# SiC462_12V_6A.net
KiCad netlist of a schematic drawn in Altium Designer
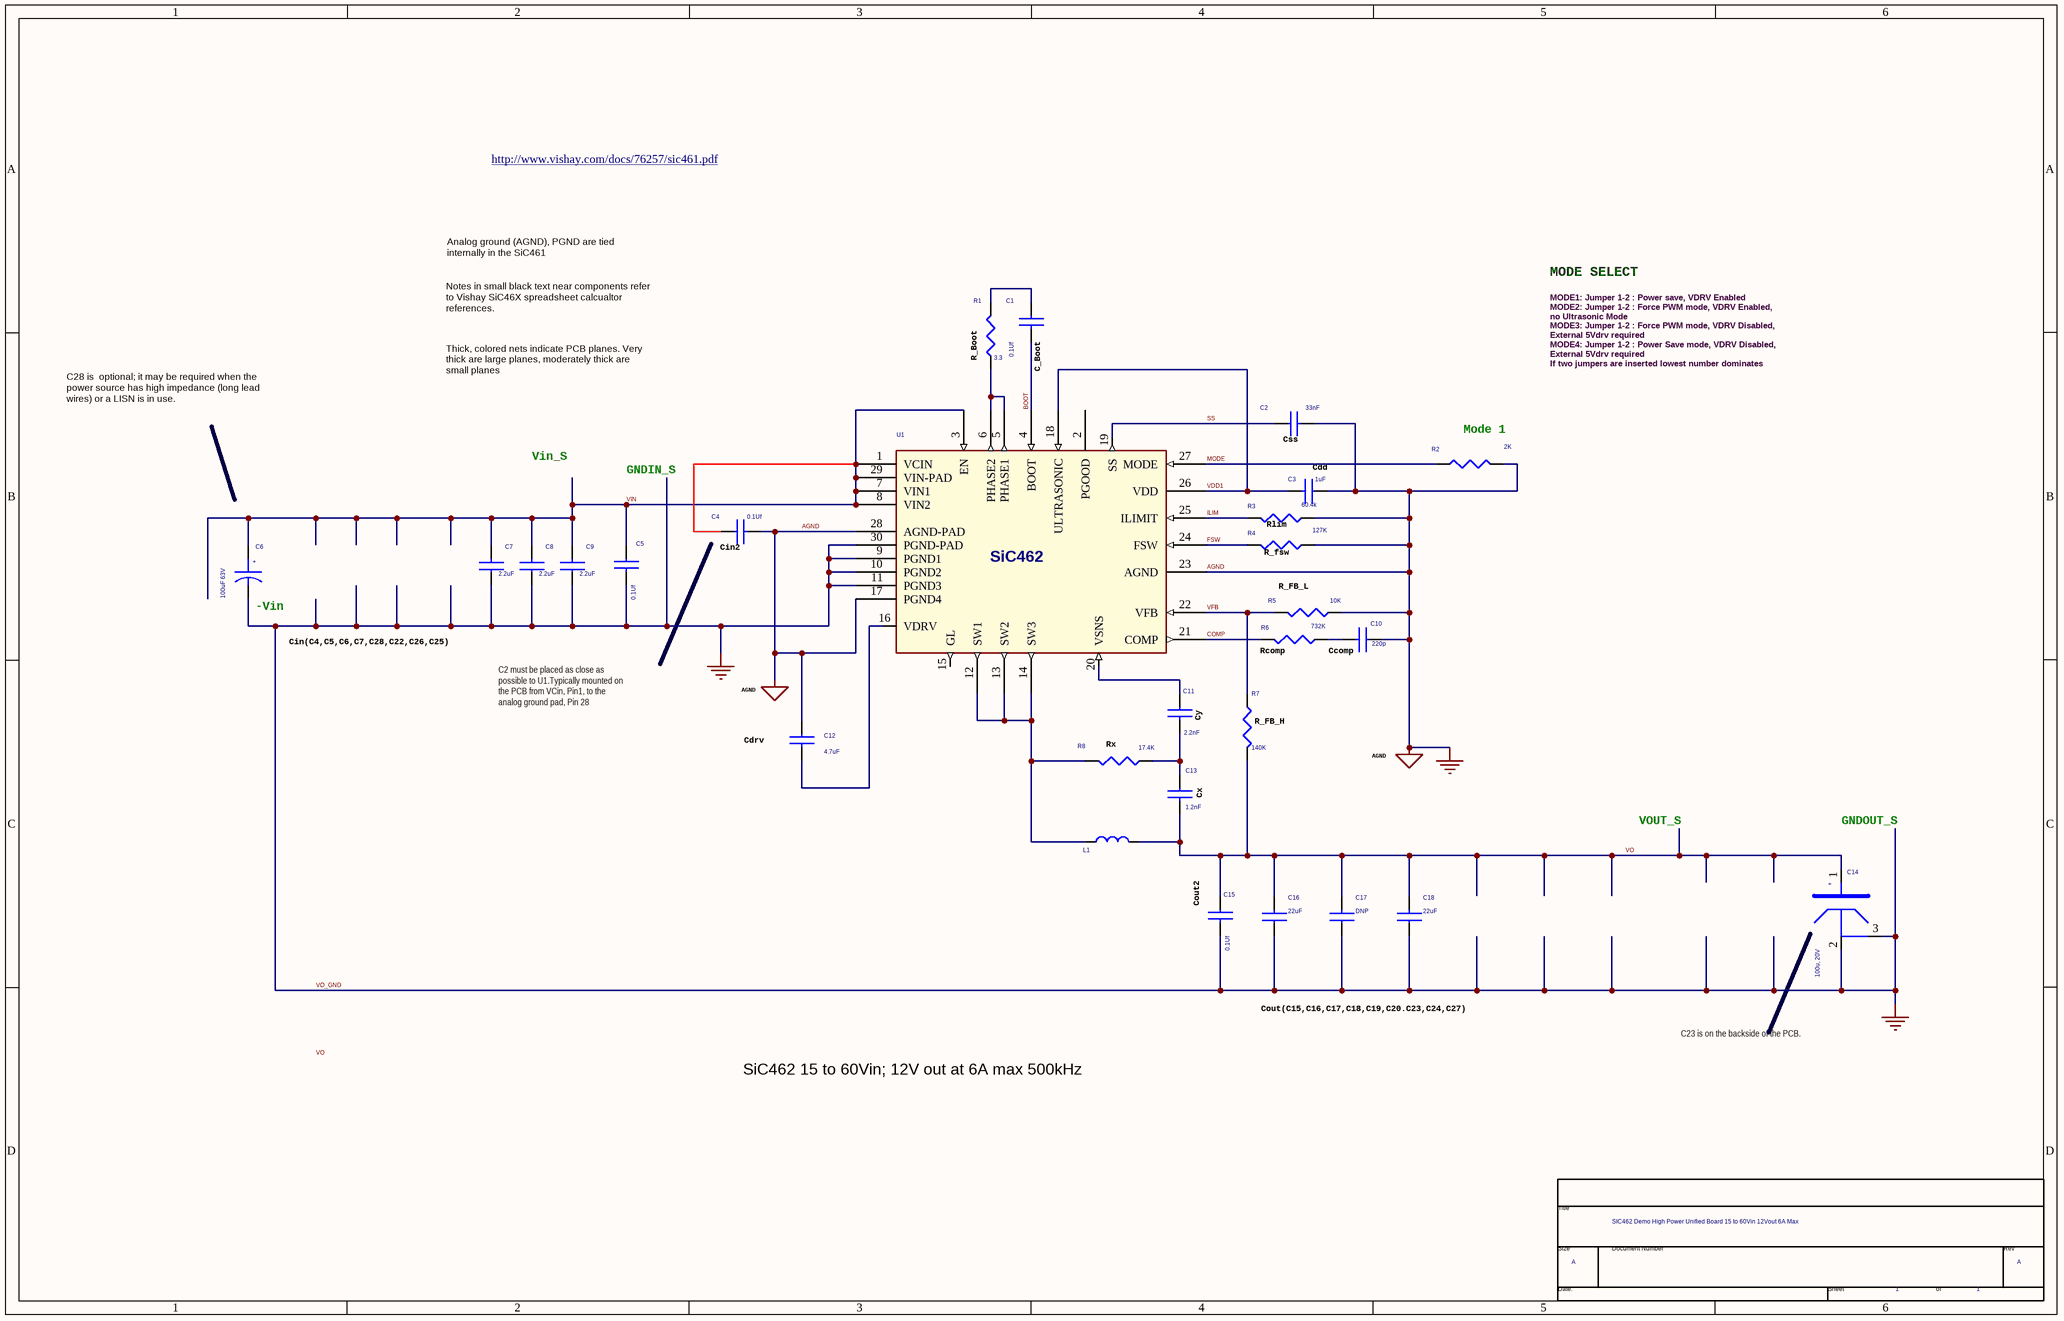
[diagram p0: SiC462 12V 6A.SchDoc]

(export (version "E")
  (design (tool "Eeschema 10.0.6"))
  (components
    (comp (ref "*")
      (value "TitleBlock0")
      (fields
        (field (name "REVCODE") "A")
        (field (name "TITLE") "SIC462 Demo High Power Unified Board 15 to 60Vin 12Vout 6A Max")
        (field (name "PAGE SIZE") "A")
        (field (name "PAGE NUMBER") "1")
        (field (name "PAGE COUNT") "1")
      )
      (libsource (lib "*") (part "TitleBlock0"))
    )
    (comp (ref "C1")
      (value "0.1Uf")
      (footprint "RR_0603")
      (description "Ceramic Cap, 0.1uF,100volts, X7S, 10%, 0603")
      (fields (field (name "TOLERANCE") "10%") (field (name "MFR") "Murata Electronics"))
      (libsource (lib "*") (part "CAP NP"))
    )
    (comp (ref "C2")
      (value "33nF")
      (footprint "RR_0603")
      (description "Ceramic Cap, 0.033uF,50V,X7R,0603,10%")
      (fields (field (name "MFR PART NUMBER") "VJ0603Y333KXACW1BC") (field (name "VOLTAGE") "50V"))
      (libsource (lib "*") (part "CAP NP"))
    )
    (comp (ref "C3")
      (value "1uF")
      (footprint "RR_0603")
      (description "Ceramic Cap, 1uF,50V, X7R,0603,10%")
      (fields
        (field (name "MANUFACTURER") "Taiyo Yuden")
        (field (name "MANUFACTURER PART") "UMK107AB7105KA-T")
      )
      (libsource (lib "*") (part "CAP NP"))
    )
    (comp (ref "C4")
      (value "0.1Uf")
      (footprint "RR_0603")
      (description "Ceramic Cap, 0.1uF,100volts, X7S, 10%, 0603")
      (fields (field (name "TOLERANCE") "10%") (field (name "MFR") "Murata Electronics"))
      (libsource (lib "*") (part "CAP NP"))
    )
    (comp (ref "C5")
      (value "0.1Uf")
      (footprint "RR_0603")
      (description "Ceramic Cap, 0.1uF,100volts, X7S, 10%, 0603")
      (fields
        (field (name "MFR PART NUMBER") "C1608X7S2A104K080AB")
        (field (name "MFR") "Murata Electronics")
      )
      (libsource (lib "*") (part "CAP NP"))
    )
    (comp (ref "C6")
      (value "100uF 63V")
      (footprint "RR_CAP-RAD-D10x9")
      (description "CAP, alum, 100uF, 63volt, 105C, 10x12, 4khr")
      (fields (field (name "MFR PART NUMBER") "MAL215058101E3") (field (name "MFR") "Vishay"))
      (libsource (lib "*") (part "CAP POL"))
    )
    (comp (ref "C7")
      (value "2.2uF")
      (footprint "RR_1210")
      (description "Ceramic Cap, 2.2uF,100volts, X7R, 10%, 1210")
      (fields (field (name "MFR PART NUMBER") "GRM32ER72A225KA35K") (field (name "MFR") "Murata Electronics"))
      (libsource (lib "*") (part "CAP NP"))
    )
    (comp (ref "C8")
      (value "2.2uF")
      (footprint "RR_1210")
      (description "Ceramic Cap, 2.2uF,100volts, X7R, 10%, 1210")
      (fields (field (name "MFR") "Murata Electronics") (field (name "MFR PART NUMBER") "GRM32ER72A225KA35K"))
      (libsource (lib "*") (part "CAP NP"))
    )
    (comp (ref "C9")
      (value "2.2uF")
      (footprint "RR_1210")
      (description "Ceramic Cap, 2.2uF,100volts, X7R, 10%, 1210")
      (fields (field (name "MFR PART NUMBER") "GRM32ER72A225KA35K") (field (name "MFR") "Murata Electronics"))
      (libsource (lib "*") (part "CAP NP"))
    )
    (comp (ref "C10")
      (value "220p")
      (footprint "RR_0603")
      (description "Ceramic Cap, 220p,100V,COG,0603, 5%")
      (fields (field (name "MANUFACTURER") "Vishay") (field (name "MANUFACTURER PART") "VJ0603A221JXBPW1BC"))
      (libsource (lib "*") (part "CAP NP"))
    )
    (comp (ref "C11")
      (value "2.2nF")
      (footprint "RR_0603")
      (description "Ceramic Cap, 2200pF,100V,X7R,0603, 5%")
      (fields (field (name "MFR") "Vishay") (field (name "TOLERANCE") "5%"))
      (libsource (lib "*") (part "CAP NP"))
    )
    (comp (ref "C12")
      (value "4.7uF")
      (footprint "RR_1206")
      (description "Ceramic Cap, 4.7uF,25V,X6S,10%,0603")
      (fields (field (name "MFR") "Murata") (field (name "TOLERANCE") "10%"))
      (libsource (lib "*") (part "CAP NP"))
    )
    (comp (ref "C13")
      (value "1.2nF")
      (footprint "RR_0603")
      (description "Ceramic Cap, 1.2nF,100V,X7R,0805, 10%")
      (fields (field (name "MANUFACTURER") "Vishay") (field (name "MANUFACTURER PART") "VJ0805Y122KXBPW1BC"))
      (libsource (lib "*") (part "CAP NP"))
    )
    (comp (ref "C14")
      (value "100u, 20V")
      (footprint "RR_CAP-RAD-D10x9")
      (description "Polymer SMD 20volts 100uF ESR 55mohm 7343")
      (fields (field (name "MFR PART NUMBER") "20TQC100MYF") (field (name "MFR") "Panasonic"))
      (libsource (lib "*") (part "CAP, TA-P,V,470u, 2V_0"))
    )
    (comp (ref "C15")
      (value "0.1Uf")
      (footprint "RR_0805")
      (description "Ceramic Cap, 0.1uF,100volts, X7S, 10%, 0603")
      (fields
        (field (name "MFR PART NUMBER") "C1608X7S2A104K080AB")
        (field (name "MFR") "Murata Electronics")
      )
      (libsource (lib "*") (part "CAP NP"))
    )
    (comp (ref "C16")
      (value "22uF")
      (footprint "RR_1206")
      (description "Ceramic Cap, 22uF,25volts,X7R,10%,1206")
      (fields (field (name "MFR") "AVX Corporation") (field (name "TOLERANCE") "10%"))
      (libsource (lib "*") (part "CAP NP"))
    )
    (comp (ref "C17")
      (value "DNP")
      (footprint "RR_1206")
      (description "Ceramic Cap, 22uF,25volts,X7R,10%,1206")
      (fields (field (name "MFR PART NUMBER") "12061C225KAT2A") (field (name "VOLTAGE") "100V"))
      (libsource (lib "*") (part "CAP NP"))
    )
    (comp (ref "C18")
      (value "22uF")
      (footprint "RR_1206")
      (description "Ceramic Cap, 22uF,25volts,X7R,10%,1206")
      (fields (field (name "MFR") "AVX Corporation") (field (name "TOLERANCE") "10%"))
      (libsource (lib "*") (part "CAP NP"))
    )
    (comp (ref "L1")
      (value "~")
      (footprint "RR_IND_CMD_12x12")
      (description "INDUCTOR, 3.3uH,20%,14m DCR,18.6A Saturation")
      (fields (field (name "MFR PART NUMBER") "IHLP4040DZER100M01") (field (name "MANUFACTURER") "Vishay"))
      (libsource (lib "*") (part "IND"))
    )
    (comp (ref "R1")
      (value "3.3")
      (footprint "RR_0603")
      (description "SMD,3.3Ohm, 1% 0603")
      (fields
        (field (name "MAN PART NUMBER") "CRCW06033R30FKEA")
        (field (name "MANUFACTURER PART") "CRCW06030000ZSTA")
      )
      (libsource (lib "*") (part "RESISTOR"))
    )
    (comp (ref "R2")
      (value "2K")
      (footprint "RR_0603")
      (description "SMD,2K,1%,0603")
      (fields (field (name "MANUFACTURER") "Vishay") (field (name "MANUFACTURER PART") "CRCW06032K00FKEB"))
      (libsource (lib "*") (part "RESISTOR"))
    )
    (comp (ref "R3")
      (value "60.4k")
      (footprint "RR_0603")
      (description "SMD,60.4K,1%,0603")
      (fields (field (name "MANUFACTURER") "Vishay") (field (name "MANUFACTURER PART") "CRCW060360K4FKEA"))
      (libsource (lib "*") (part "RESISTOR"))
    )
    (comp (ref "R4")
      (value "127K")
      (footprint "RR_0603")
      (description "SMD,127K,1%,0603 100PPM")
      (fields (field (name "MANUFACTURER") "Vishay") (field (name "MANUFACTURER PART") "CRCW0603127KFKEA"))
      (libsource (lib "*") (part "RESISTOR"))
    )
    (comp (ref "R5")
      (value "10K")
      (footprint "RR_0603")
      (description "SMD,10K,1%,0603")
      (fields (field (name "MANUFACTURER") "Vishay") (field (name "MANUFACTURER PART") "CRCW060310K0FKTA"))
      (libsource (lib "*") (part "RESISTOR"))
    )
    (comp (ref "R6")
      (value "732K")
      (footprint "RR_0603")
      (description "SMD 1/10watt 732 kOhms 1%,0603")
      (fields (field (name "MFR") "Vishay Dale") (field (name "TOLERANCE") "1%"))
      (libsource (lib "*") (part "RESISTOR"))
    )
    (comp (ref "R7")
      (value "140K")
      (footprint "RR_0603")
      (description "SMD 1,10W 140K Ohms 1% 0603")
      (fields (field (name "MANUFACTURER") "Vishay") (field (name "MANUFACTURER PART") "CRCW0603140KFKEA"))
      (libsource (lib "*") (part "RESISTOR"))
    )
    (comp (ref "R8")
      (value "17.4K")
      (footprint "RR_0603")
      (description "Resistors - SMD 1/8watt 17.4Kohms 1% 0805")
      (fields (field (name "MFR") "Vishay Dale") (field (name "TOLERANCE") "1%"))
      (libsource (lib "*") (part "RESISTOR"))
    )
    (comp (ref "U1")
      (value "SiC462")
      (footprint "SIC462")
      (description "4.5~60V,6A, High Voltage microBuck")
      (fields (field (name "MFR") "Vishay") (field (name "MAN PART NUMBER") "SiC462ED-T1-GE3"))
      (libsource (lib "*") (part "SiC462CD-T1-GE3_27"))
    )
  )
  (nets
    (net (code "1") (name "/BOOT") (class "Default")
      (node (ref "C1") (pin "2") (pinfunction "2_2") (pintype "passive"))
      (node (ref "U1") (pin "4") (pinfunction "BOOT_4") (pintype "input"))
    )
    (net (code "2") (name "/COMP") (class "Default")
      (node (ref "R6") (pin "2") (pinfunction "2_2") (pintype "passive"))
      (node (ref "U1") (pin "21") (pinfunction "COMP_21") (pintype "output"))
    )
    (net (code "3") (name "/FSW") (class "Default")
      (node (ref "R4") (pin "2") (pinfunction "2_2") (pintype "passive"))
      (node (ref "U1") (pin "24") (pinfunction "FSW_24") (pintype "input"))
    )
    (net (code "4") (name "/ILIM") (class "Default")
      (node (ref "R3") (pin "2") (pinfunction "2_2") (pintype "passive"))
      (node (ref "U1") (pin "25") (pinfunction "ILIMIT_25") (pintype "input"))
    )
    (net (code "5") (name "/MODE") (class "Default")
      (node (ref "R2") (pin "1") (pinfunction "1_1") (pintype "passive"))
      (node (ref "U1") (pin "27") (pinfunction "MODE_27") (pintype "input"))
    )
    (net (code "6") (name "/SS") (class "Default")
      (node (ref "C2") (pin "1") (pinfunction "1_1") (pintype "passive"))
      (node (ref "U1") (pin "19") (pinfunction "SS_19") (pintype "output"))
    )
    (net (code "7") (name "/VDD1") (class "Default")
      (node (ref "C3") (pin "2") (pinfunction "2_2") (pintype "passive"))
      (node (ref "U1") (pin "18") (pinfunction "ULTRASONIC_18") (pintype "input"))
      (node (ref "U1") (pin "26") (pinfunction "VDD_26") (pintype "power_in"))
    )
    (net (code "8") (name "/VFB") (class "Default")
      (node (ref "R5") (pin "2") (pinfunction "2_2") (pintype "passive"))
      (node (ref "R7") (pin "1") (pinfunction "1_1") (pintype "passive"))
      (node (ref "U1") (pin "22") (pinfunction "VFB_22") (pintype "input"))
    )
    (net (code "9") (name "/VIN") (class "Default")
      (node (ref "C4") (pin "1") (pinfunction "1_1") (pintype "passive"))
      (node (ref "C5") (pin "1") (pinfunction "1_1") (pintype "passive"))
      (node (ref "C6") (pin "1") (pinfunction "1_1") (pintype "passive"))
      (node (ref "C7") (pin "2") (pinfunction "2_2") (pintype "passive"))
      (node (ref "C8") (pin "2") (pinfunction "2_2") (pintype "passive"))
      (node (ref "C9") (pin "2") (pinfunction "2_2") (pintype "passive"))
      (node (ref "U1") (pin "1") (pinfunction "VCIN_1") (pintype "power_in"))
      (node (ref "U1") (pin "29") (pinfunction "VIN-PAD_29") (pintype "power_in"))
      (node (ref "U1") (pin "3") (pinfunction "EN_3") (pintype "input"))
      (node (ref "U1") (pin "7") (pinfunction "VIN1_7") (pintype "power_in"))
      (node (ref "U1") (pin "8") (pinfunction "VIN2_8") (pintype "power_in"))
    )
    (net (code "10") (name "/VO") (class "Default")
      (node (ref "C13") (pin "2") (pinfunction "2_2") (pintype "passive"))
      (node (ref "C14") (pin "1") (pinfunction "1_1") (pintype "passive"))
      (node (ref "C15") (pin "1") (pinfunction "1_1") (pintype "passive"))
      (node (ref "C16") (pin "2") (pinfunction "2_2") (pintype "passive"))
      (node (ref "C17") (pin "2") (pinfunction "2_2") (pintype "passive"))
      (node (ref "C18") (pin "2") (pinfunction "2_2") (pintype "passive"))
      (node (ref "L1") (pin "1") (pinfunction "A_1") (pintype "passive"))
      (node (ref "R7") (pin "2") (pinfunction "2_2") (pintype "passive"))
    )
    (net (code "11") (name "GND") (class "Default")
      (node (ref "C10") (pin "1") (pinfunction "1_1") (pintype "passive"))
      (node (ref "C12") (pin "1") (pinfunction "1_1") (pintype "passive"))
      (node (ref "C14") (pin "2") (pinfunction "2_2") (pintype "passive"))
      (node (ref "C14") (pin "3") (pinfunction "3_3") (pintype "passive"))
      (node (ref "C15") (pin "2") (pinfunction "2_2") (pintype "passive"))
      (node (ref "C16") (pin "1") (pinfunction "1_1") (pintype "passive"))
      (node (ref "C17") (pin "1") (pinfunction "1_1") (pintype "passive"))
      (node (ref "C18") (pin "1") (pinfunction "1_1") (pintype "passive"))
      (node (ref "C2") (pin "2") (pinfunction "2_2") (pintype "passive"))
      (node (ref "C3") (pin "1") (pinfunction "1_1") (pintype "passive"))
      (node (ref "C4") (pin "2") (pinfunction "2_2") (pintype "passive"))
      (node (ref "C5") (pin "2") (pinfunction "2_2") (pintype "passive"))
      (node (ref "C6") (pin "2") (pinfunction "2_2") (pintype "passive"))
      (node (ref "C7") (pin "1") (pinfunction "1_1") (pintype "passive"))
      (node (ref "C8") (pin "1") (pinfunction "1_1") (pintype "passive"))
      (node (ref "C9") (pin "1") (pinfunction "1_1") (pintype "passive"))
      (node (ref "R2") (pin "2") (pinfunction "2_2") (pintype "passive"))
      (node (ref "R3") (pin "1") (pinfunction "1_1") (pintype "passive"))
      (node (ref "R4") (pin "1") (pinfunction "1_1") (pintype "passive"))
      (node (ref "R5") (pin "1") (pinfunction "1_1") (pintype "passive"))
      (node (ref "U1") (pin "10") (pinfunction "PGND2_10") (pintype "power_in"))
      (node (ref "U1") (pin "11") (pinfunction "PGND3_11") (pintype "power_in"))
      (node (ref "U1") (pin "17") (pinfunction "PGND4_17") (pintype "power_in"))
      (node (ref "U1") (pin "23") (pinfunction "AGND_23") (pintype "power_in"))
      (node (ref "U1") (pin "28") (pinfunction "AGND-PAD_28") (pintype "power_in"))
      (node (ref "U1") (pin "30") (pinfunction "PGND-PAD_30") (pintype "passive"))
      (node (ref "U1") (pin "9") (pinfunction "PGND1_9") (pintype "power_in"))
    )
    (net (code "12") (name "Net-(C1-Pad1)") (class "Default")
      (node (ref "C1") (pin "1") (pinfunction "1_1") (pintype "passive"))
      (node (ref "R1") (pin "2") (pinfunction "2_2") (pintype "passive"))
    )
    (net (code "13") (name "Net-(C10-Pad2)") (class "Default")
      (node (ref "C10") (pin "2") (pinfunction "2_2") (pintype "passive"))
      (node (ref "R6") (pin "1") (pinfunction "1_1") (pintype "passive"))
    )
    (net (code "14") (name "Net-(C11-Pad2)") (class "Default")
      (node (ref "C11") (pin "2") (pinfunction "2_2") (pintype "passive"))
      (node (ref "C13") (pin "1") (pinfunction "1_1") (pintype "passive"))
      (node (ref "R8") (pin "1") (pinfunction "1_1") (pintype "passive"))
    )
    (net (code "15") (name "Net-(L1-B)") (class "Default")
      (node (ref "L1") (pin "2") (pinfunction "B_2") (pintype "passive"))
      (node (ref "R8") (pin "2") (pinfunction "2_2") (pintype "passive"))
      (node (ref "U1") (pin "12") (pinfunction "SW1_12") (pintype "output"))
      (node (ref "U1") (pin "13") (pinfunction "SW2_13") (pintype "output"))
      (node (ref "U1") (pin "14") (pinfunction "SW3_14") (pintype "output"))
    )
    (net (code "16") (name "Net-(U1-PHASE1)") (class "Default")
      (node (ref "R1") (pin "1") (pinfunction "1_1") (pintype "passive"))
      (node (ref "U1") (pin "5") (pinfunction "PHASE1_5") (pintype "output"))
      (node (ref "U1") (pin "6") (pinfunction "PHASE2_6") (pintype "output"))
    )
    (net (code "17") (name "Net-(U1-VDRV)") (class "Default")
      (node (ref "C12") (pin "2") (pinfunction "2_2") (pintype "passive"))
      (node (ref "U1") (pin "16") (pinfunction "VDRV_16") (pintype "power_in"))
    )
    (net (code "18") (name "Net-(U1-VSNS)") (class "Default")
      (node (ref "C11") (pin "1") (pinfunction "1_1") (pintype "passive"))
      (node (ref "U1") (pin "20") (pinfunction "VSNS_20") (pintype "input"))
    )
    (net (code "19") (name "unconnected-(U1-GL-Pad15)") (class "Default")
      (node (ref "U1") (pin "15") (pinfunction "GL_15") (pintype "output"))
    )
    (net (code "20") (name "unconnected-(U1-PGOOD-Pad2)") (class "Default")
      (node (ref "U1") (pin "2") (pinfunction "PGOOD_2") (pintype "open_collector"))
    )
  )
)
